# Sheet1.net
KiCad netlist of a schematic drawn in Altium Designer
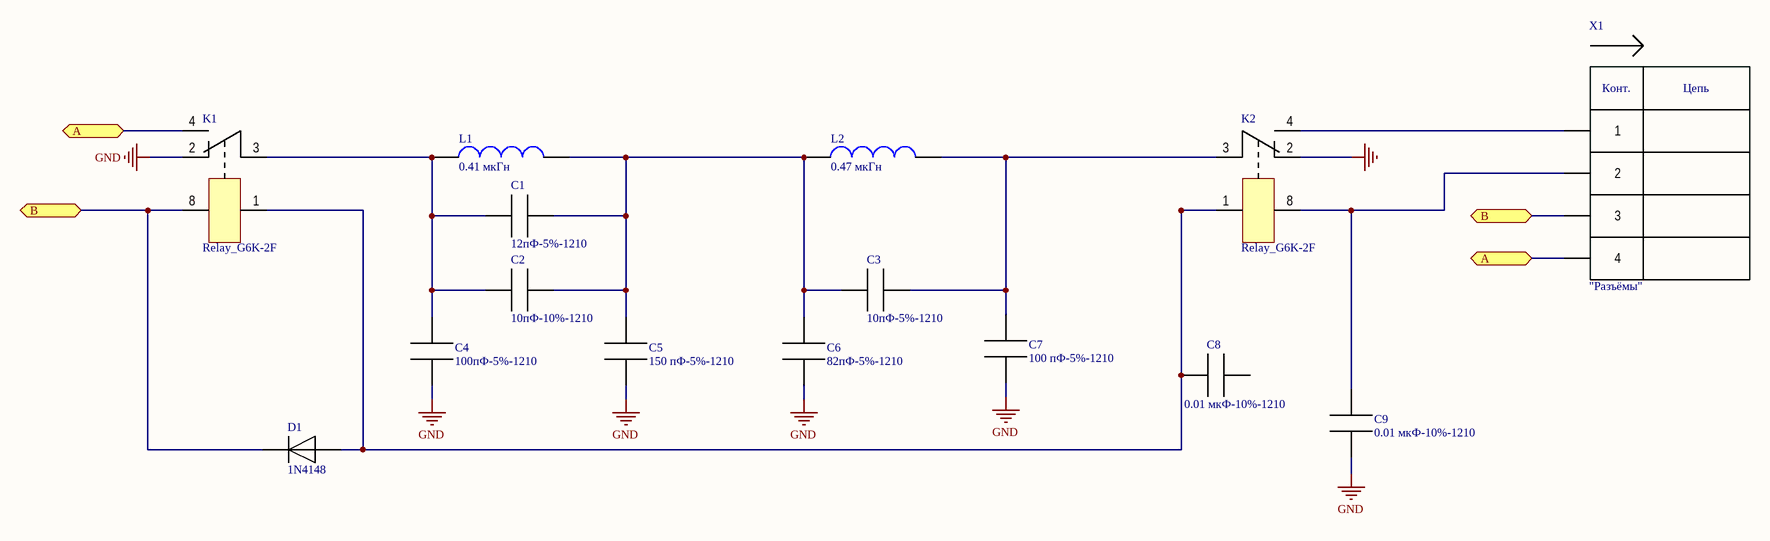
[diagram p0: Sheet1.SchDoc]

(export (version "E")
  (design (tool "Eeschema 10.0.6"))
  (components
    (comp (ref "C1")
      (value "12пФ-5%-1210")
      (footprint "Capacitor_0805")
      (fields (field (name "MANUFACTURER") "Kyocera AVX") (field (name "PARTNUMBER") "KGQ32DCG2D120JT"))
      (libsource (lib "Schlib1") (part "Capasitor_SMD1210C"))
    )
    (comp (ref "C2")
      (value "10пФ-10%-1210")
      (footprint "Capacitor_0805")
      (fields
        (field (name "MANUFACTURER") "Kemet Electronics")
        (field (name "PARTNUMBER") "C1210C100K9RACTU")
      )
      (libsource (lib "Schlib1") (part "Capasitor_SMD1210C"))
    )
    (comp (ref "C3")
      (value "10пФ-5%-1210")
      (footprint "Capacitor_0805")
      (fields
        (field (name "MANUFACTURER") "Kemet Electronics")
        (field (name "PARTNUMBER") "C1210C100K9RACTU")
      )
      (libsource (lib "Schlib1") (part "Capasitor_SMD1210C"))
    )
    (comp (ref "C4")
      (value "100пФ-5%-1210")
      (footprint "Capacitor_0805")
      (fields
        (field (name "MANUFACTURER") "Murata Electronics")
        (field (name "PARTNUMBER") "GRM32A7U3D101JW31D")
      )
      (libsource (lib "Schlib1") (part "Capasitor_SMD1210C"))
    )
    (comp (ref "C5")
      (value "150 пФ-5%-1210")
      (footprint "Capacitor_0805")
      (fields
        (field (name "MANUFACTURER") "Kemet Electronics")
        (field (name "PARTNUMBER") "C1210X151J1HACAUTO")
      )
      (libsource (lib "Schlib1") (part "Capasitor_SMD1210C"))
    )
    (comp (ref "C6")
      (value "82пФ-5%-1210")
      (footprint "Capacitor_0805")
      (fields
        (field (name "MANUFACTURER") "Murata Electronics")
        (field (name "PARTNUMBER") "GRM32A7U3D820JW31D")
      )
      (libsource (lib "Schlib1") (part "Capasitor_SMD1210C"))
    )
    (comp (ref "C7")
      (value "100 пФ-5%-1210")
      (footprint "Capacitor_0805")
      (fields
        (field (name "MANUFACTURER") "Murata Electronics")
        (field (name "PARTNUMBER") "GRM32A7U3D101JW31D")
      )
      (libsource (lib "Schlib1") (part "Capasitor_SMD1210C"))
    )
    (comp (ref "C8")
      (value "0.01 мкФ-10%-1210")
      (footprint "Capacitor_0805")
      (fields
        (field (name "MANUFACTURER") "Murata Electronics")
        (field (name "PARTNUMBER") "GRM32DR72E104KW01L")
      )
      (libsource (lib "Schlib1") (part "Capasitor_SMD1210C"))
    )
    (comp (ref "C9")
      (value "0.01 мкФ-10%-1210")
      (footprint "Capacitor_0805")
      (fields
        (field (name "MANUFACTURER") "Murata Electronics")
        (field (name "PARTNUMBER") "GRM32DR72E104KW01L")
      )
      (libsource (lib "Schlib1") (part "Capasitor_SMD1210C"))
    )
    (comp (ref "D1")
      (value "1N4148")
      (footprint "1N4148_MELF")
      (libsource (lib "Schlib1_3") (part "Diode_1N4148"))
    )
    (comp (ref "K1")
      (value "Relay_G6K-2F")
      (footprint "Relay_G6K-2F")
      (libsource (lib "") (part "Relay_G6K-2F_1"))
    )
    (comp (ref "K2")
      (value "Relay_G6K-2F")
      (footprint "Relay_G6K-2F")
      (libsource (lib "Schlib1_3") (part "Relay_G6K-2F"))
    )
    (comp (ref "L1")
      (value "0.41 мкГн")
      (footprint "Inductor_1210L")
      (libsource (lib "Schlib1_3") (part "Inductor_1210"))
    )
    (comp (ref "L2")
      (value "0.47 мкГн")
      (footprint "Inductor_1210L")
      (libsource (lib "Schlib1_3") (part "Inductor_1210"))
    )
    (comp (ref "X1")
      (value "\"Разъёмы\"")
      (footprint "PLS-1x4")
      (fields (field (name "PARTNUMBER") "DS-1021-1x4SF11-B"))
      (libsource (lib "Schlib1_3") (part "PLS-1x4"))
    )
  )
  (nets
    (net (code "1") (name "/A") (class "Default")
      (node (ref "K1") (pin "4") (pintype "passive"))
      (node (ref "X1") (pin "4") (pinfunction "4_4") (pintype "passive"))
    )
    (net (code "2") (name "/B") (class "Default")
      (node (ref "D1") (pin "2") (pinfunction "2_2") (pintype "passive"))
      (node (ref "K1") (pin "8") (pinfunction "minus_8") (pintype "passive"))
      (node (ref "X1") (pin "3") (pinfunction "3_3") (pintype "passive"))
    )
    (net (code "3") (name "<NO NET>") (class "Default") (node (ref "K2") (pin "2") (pintype "passive")))
    (net (code "4") (name "GND") (class "Default")
      (node (ref "C4") (pin "0") (pinfunction "0_0") (pintype "passive"))
      (node (ref "C5") (pin "0") (pinfunction "0_0") (pintype "passive"))
      (node (ref "C6") (pin "0") (pinfunction "0_0") (pintype "passive"))
      (node (ref "C7") (pin "1") (pinfunction "1_1") (pintype "passive"))
      (node (ref "C9") (pin "0") (pinfunction "0_0") (pintype "passive"))
      (node (ref "K1") (pin "2") (pintype "passive"))
    )
    (net (code "5") (name "Net-(C1-Pad0)") (class "Default")
      (node (ref "C1") (pin "0") (pinfunction "0_0") (pintype "passive"))
      (node (ref "C2") (pin "0") (pinfunction "0_0") (pintype "passive"))
      (node (ref "C4") (pin "1") (pinfunction "1_1") (pintype "passive"))
      (node (ref "K1") (pin "3") (pintype "passive"))
      (node (ref "L1") (pin "1") (pinfunction "1_1") (pintype "passive"))
    )
    (net (code "6") (name "Net-(C1-Pad1)") (class "Default")
      (node (ref "C1") (pin "1") (pinfunction "1_1") (pintype "passive"))
      (node (ref "C2") (pin "1") (pinfunction "1_1") (pintype "passive"))
      (node (ref "C3") (pin "0") (pinfunction "0_0") (pintype "passive"))
      (node (ref "C5") (pin "1") (pinfunction "1_1") (pintype "passive"))
      (node (ref "C6") (pin "1") (pinfunction "1_1") (pintype "passive"))
      (node (ref "L1") (pin "2") (pinfunction "2_2") (pintype "passive"))
      (node (ref "L2") (pin "1") (pinfunction "1_1") (pintype "passive"))
    )
    (net (code "7") (name "Net-(C3-Pad1)") (class "Default")
      (node (ref "C3") (pin "1") (pinfunction "1_1") (pintype "passive"))
      (node (ref "C7") (pin "0") (pinfunction "0_0") (pintype "passive"))
      (node (ref "K2") (pin "3") (pintype "passive"))
      (node (ref "L2") (pin "2") (pinfunction "2_2") (pintype "passive"))
    )
    (net (code "8") (name "Net-(K1-plus)") (class "Default")
      (node (ref "C8") (pin "0") (pinfunction "0_0") (pintype "passive"))
      (node (ref "D1") (pin "1") (pinfunction "1_1") (pintype "passive"))
      (node (ref "K1") (pin "1") (pinfunction "plus_1") (pintype "passive"))
      (node (ref "K2") (pin "1") (pinfunction "plus_1") (pintype "passive"))
    )
    (net (code "9") (name "Net-(K2-Pad4)") (class "Default")
      (node (ref "K2") (pin "4") (pintype "passive"))
      (node (ref "X1") (pin "1") (pinfunction "1_1") (pintype "passive"))
    )
    (net (code "10") (name "Net-(K2-minus)") (class "Default")
      (node (ref "C9") (pin "1") (pinfunction "1_1") (pintype "passive"))
      (node (ref "K2") (pin "8") (pinfunction "minus_8") (pintype "passive"))
      (node (ref "X1") (pin "2") (pinfunction "2_2") (pintype "passive"))
    )
    (net (code "11") (name "unconnected-(C8-Pad1)") (class "Default")
      (node (ref "C8") (pin "1") (pinfunction "1_1") (pintype "passive"))
    )
  )
)
